# DCSource3V3.net
KiCad netlist of a schematic drawn in Altium Designer
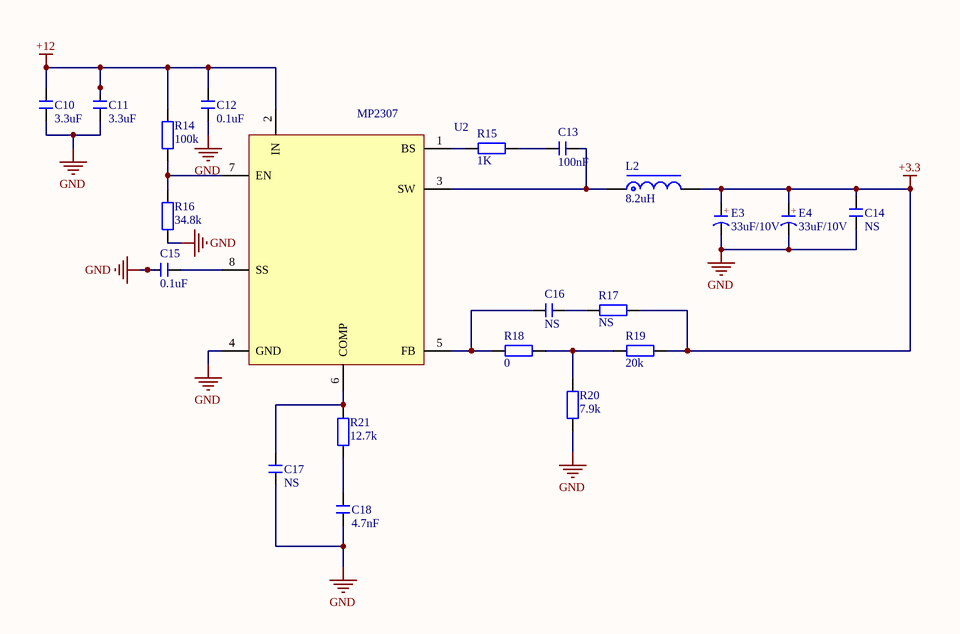
[diagram p0: DCSource3V3.SchDoc]

(export (version "E")
  (design (tool "Eeschema 10.0.6"))
  (components
    (comp (ref "C10")
      (value "3.3uF")
      (footprint "C 0805_L")
      (description "无极性贴片电容")
      (libsource (lib "电容-电阻-电感-电位器") (part "C"))
    )
    (comp (ref "C11")
      (value "3.3uF")
      (footprint "C 0805_L")
      (description "无极性贴片电容")
      (libsource (lib "电容-电阻-电感-电位器") (part "C"))
    )
    (comp (ref "C12")
      (value "0.1uF")
      (footprint "C 0805_L")
      (description "无极性贴片电容")
      (libsource (lib "电容-电阻-电感-电位器") (part "C"))
    )
    (comp (ref "C13")
      (value "100nF")
      (footprint "C 0805_L")
      (description "无极性贴片电容")
      (libsource (lib "电容-电阻-电感-电位器") (part "C"))
    )
    (comp (ref "C14")
      (value "NS")
      (footprint "C 0805_L")
      (description "无极性贴片电容")
      (libsource (lib "电容-电阻-电感-电位器") (part "C"))
    )
    (comp (ref "C15")
      (value "0.1uF")
      (footprint "C 0805_L")
      (description "无极性贴片电容")
      (libsource (lib "电容-电阻-电感-电位器") (part "C"))
    )
    (comp (ref "C16")
      (value "NS")
      (footprint "C 0805_L")
      (description "无极性贴片电容")
      (libsource (lib "电容-电阻-电感-电位器") (part "C"))
    )
    (comp (ref "C17")
      (value "NS")
      (footprint "C 0805_L")
      (description "无极性贴片电容")
      (libsource (lib "电容-电阻-电感-电位器") (part "C"))
    )
    (comp (ref "C18")
      (value "4.7nF")
      (footprint "C 0805_L")
      (description "无极性贴片电容")
      (libsource (lib "电容-电阻-电感-电位器") (part "C"))
    )
    (comp (ref "E3")
      (value "33uF/10V")
      (footprint "CT 5*6 - C")
      (description "贴片固态电容")
      (libsource (lib "电容-电阻-电感-电位器") (part "C-CT"))
    )
    (comp (ref "E4")
      (value "33uF/10V")
      (footprint "CT 5*6 - C")
      (description "贴片固态电容")
      (libsource (lib "电容-电阻-电感-电位器") (part "C-CT"))
    )
    (comp (ref "L2")
      (value "8.2uH")
      (footprint "CD31")
      (description "贴片功率电感")
      (libsource (lib "电容-电阻-电感-电位器") (part "L-CD"))
    )
    (comp (ref "R14")
      (value "100k")
      (footprint "R 0805_L")
      (description "贴片电阻")
      (libsource (lib "电容-电阻-电感-电位器") (part "R"))
    )
    (comp (ref "R15")
      (value "1K")
      (footprint "R 0805_L")
      (description "贴片电阻")
      (libsource (lib "电容-电阻-电感-电位器") (part "R"))
    )
    (comp (ref "R16")
      (value "34.8k")
      (footprint "R 0805_L")
      (description "贴片电阻")
      (libsource (lib "电容-电阻-电感-电位器") (part "R"))
    )
    (comp (ref "R17")
      (value "NS")
      (footprint "R 0805_L")
      (description "贴片电阻")
      (libsource (lib "电容-电阻-电感-电位器") (part "R"))
    )
    (comp (ref "R18")
      (value "0")
      (footprint "R 0805_L")
      (description "贴片电阻")
      (libsource (lib "电容-电阻-电感-电位器") (part "R"))
    )
    (comp (ref "R19")
      (value "20k")
      (footprint "R 0805_L")
      (description "贴片电阻")
      (libsource (lib "电容-电阻-电感-电位器") (part "R"))
    )
    (comp (ref "R20")
      (value "7.9k")
      (footprint "R 0805_L")
      (description "贴片电阻")
      (libsource (lib "电容-电阻-电感-电位器") (part "R"))
    )
    (comp (ref "R21")
      (value "12.7k")
      (footprint "R 0805_L")
      (description "贴片电阻")
      (libsource (lib "电容-电阻-电感-电位器") (part "R"))
    )
    (comp (ref "U2") (value "MP2307") (footprint "SOP8_M") (libsource (lib "Schlib1") (part "Component_1")))
  )
  (nets
    (net (code "1") (name "+3.3") (class "Default")
      (node (ref "C14") (pin "2") (pinfunction "2_2") (pintype "passive"))
      (node (ref "E3") (pin "1") (pinfunction "A_1") (pintype "passive"))
      (node (ref "E4") (pin "1") (pinfunction "A_1") (pintype "passive"))
      (node (ref "L2") (pin "2") (pinfunction "2_2") (pintype "passive"))
      (node (ref "R17") (pin "1") (pinfunction "1_1") (pintype "passive"))
      (node (ref "R19") (pin "2") (pinfunction "2_2") (pintype "passive"))
    )
    (net (code "2") (name "+12") (class "Default")
      (node (ref "C10") (pin "2") (pinfunction "2_2") (pintype "passive"))
      (node (ref "C11") (pin "2") (pinfunction "2_2") (pintype "passive"))
      (node (ref "C12") (pin "2") (pinfunction "2_2") (pintype "passive"))
      (node (ref "R14") (pin "2") (pinfunction "2_2") (pintype "passive"))
      (node (ref "U2") (pin "2") (pinfunction "IN_2") (pintype "passive"))
    )
    (net (code "3") (name "GND") (class "Default")
      (node (ref "C10") (pin "1") (pinfunction "1_1") (pintype "passive"))
      (node (ref "C11") (pin "1") (pinfunction "1_1") (pintype "passive"))
      (node (ref "C12") (pin "1") (pinfunction "1_1") (pintype "passive"))
      (node (ref "C14") (pin "1") (pinfunction "1_1") (pintype "passive"))
      (node (ref "C15") (pin "2") (pinfunction "2_2") (pintype "passive"))
      (node (ref "C17") (pin "1") (pinfunction "1_1") (pintype "passive"))
      (node (ref "C18") (pin "1") (pinfunction "1_1") (pintype "passive"))
      (node (ref "E3") (pin "2") (pinfunction "K_2") (pintype "passive"))
      (node (ref "E4") (pin "2") (pinfunction "K_2") (pintype "passive"))
      (node (ref "R16") (pin "1") (pinfunction "1_1") (pintype "passive"))
      (node (ref "R20") (pin "1") (pinfunction "1_1") (pintype "passive"))
      (node (ref "U2") (pin "4") (pinfunction "GND_4") (pintype "passive"))
    )
    (net (code "4") (name "Net-(C13-Pad1)") (class "Default")
      (node (ref "C13") (pin "1") (pinfunction "1_1") (pintype "passive"))
      (node (ref "R15") (pin "2") (pinfunction "2_2") (pintype "passive"))
    )
    (net (code "5") (name "Net-(C16-Pad2)") (class "Default")
      (node (ref "C16") (pin "2") (pinfunction "2_2") (pintype "passive"))
      (node (ref "R17") (pin "2") (pinfunction "2_2") (pintype "passive"))
    )
    (net (code "6") (name "Net-(C18-Pad2)") (class "Default")
      (node (ref "C18") (pin "2") (pinfunction "2_2") (pintype "passive"))
      (node (ref "R21") (pin "1") (pinfunction "1_1") (pintype "passive"))
    )
    (net (code "7") (name "Net-(R18-Pad2)") (class "Default")
      (node (ref "R18") (pin "2") (pinfunction "2_2") (pintype "passive"))
      (node (ref "R19") (pin "1") (pinfunction "1_1") (pintype "passive"))
      (node (ref "R20") (pin "2") (pinfunction "2_2") (pintype "passive"))
    )
    (net (code "8") (name "Net-(U2-BS)") (class "Default")
      (node (ref "R15") (pin "1") (pinfunction "1_1") (pintype "passive"))
      (node (ref "U2") (pin "1") (pinfunction "BS_1") (pintype "passive"))
    )
    (net (code "9") (name "Net-(U2-COMP)") (class "Default")
      (node (ref "C17") (pin "2") (pinfunction "2_2") (pintype "passive"))
      (node (ref "R21") (pin "2") (pinfunction "2_2") (pintype "passive"))
      (node (ref "U2") (pin "6") (pinfunction "COMP_6") (pintype "passive"))
    )
    (net (code "10") (name "Net-(U2-EN)") (class "Default")
      (node (ref "R14") (pin "1") (pinfunction "1_1") (pintype "passive"))
      (node (ref "R16") (pin "2") (pinfunction "2_2") (pintype "passive"))
      (node (ref "U2") (pin "7") (pinfunction "EN_7") (pintype "passive"))
    )
    (net (code "11") (name "Net-(U2-FB)") (class "Default")
      (node (ref "C16") (pin "1") (pinfunction "1_1") (pintype "passive"))
      (node (ref "R18") (pin "1") (pinfunction "1_1") (pintype "passive"))
      (node (ref "U2") (pin "5") (pinfunction "FB_5") (pintype "passive"))
    )
    (net (code "12") (name "Net-(U2-SS)") (class "Default")
      (node (ref "C15") (pin "1") (pinfunction "1_1") (pintype "passive"))
      (node (ref "U2") (pin "8") (pinfunction "SS_8") (pintype "passive"))
    )
    (net (code "13") (name "Net-(U2-SW)") (class "Default")
      (node (ref "C13") (pin "2") (pinfunction "2_2") (pintype "passive"))
      (node (ref "L2") (pin "1") (pinfunction "1_1") (pintype "passive"))
      (node (ref "U2") (pin "3") (pinfunction "SW_3") (pintype "passive"))
    )
  )
)
